# uC.net
KiCad netlist of a schematic drawn in Altium Designer
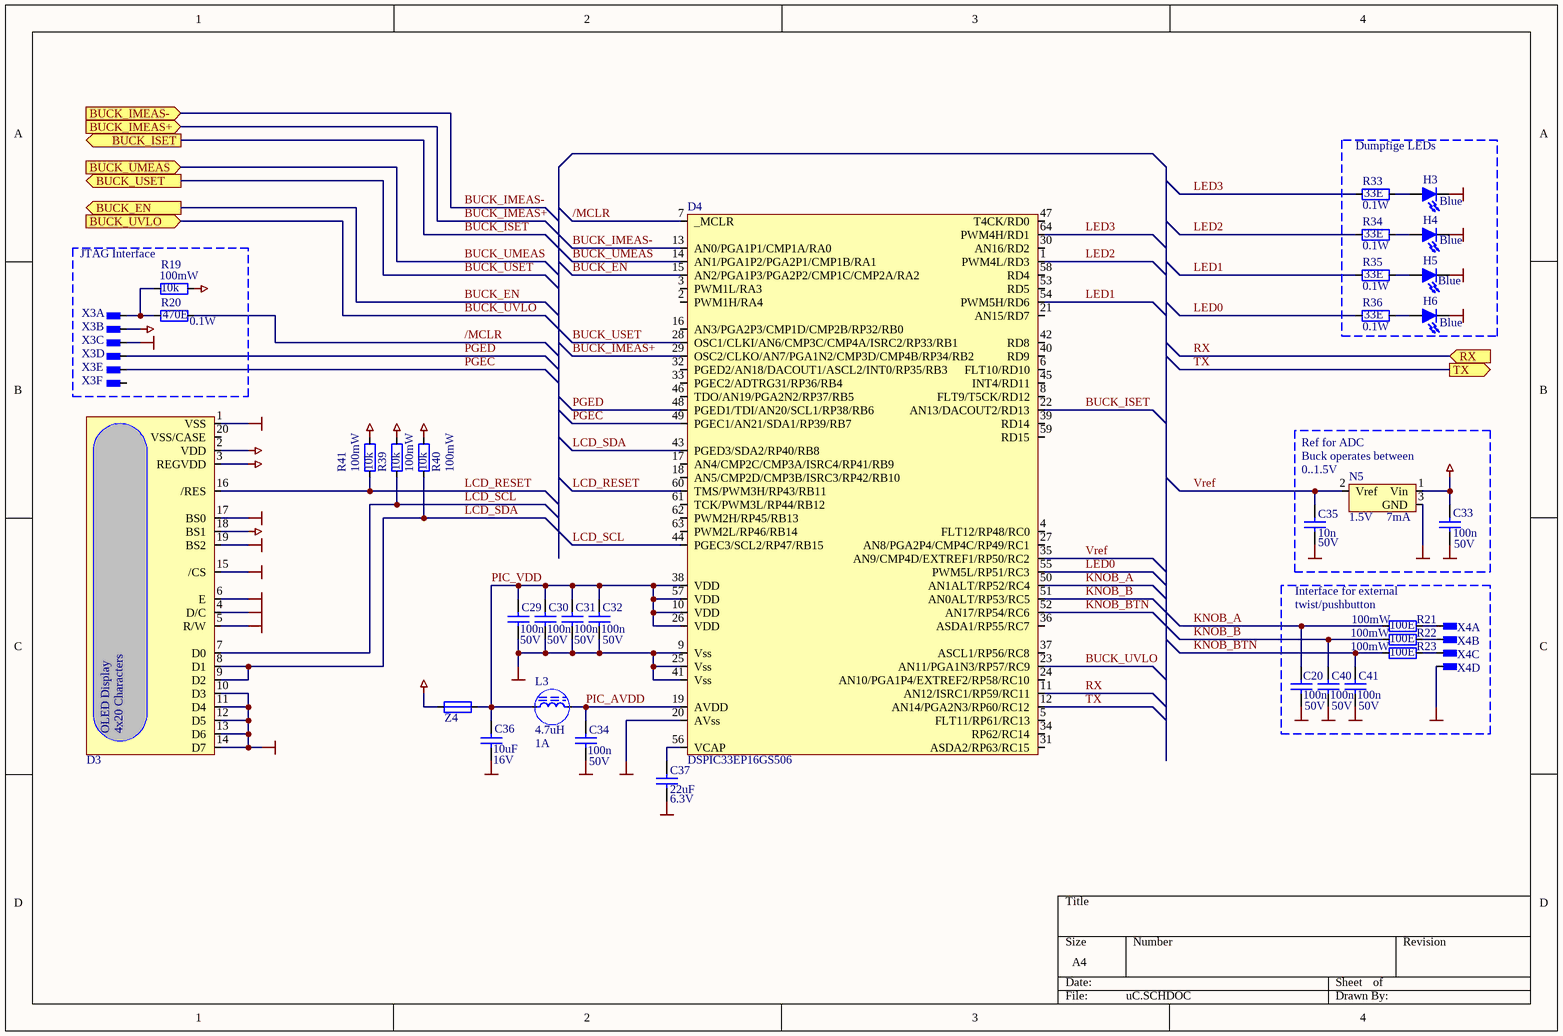
[diagram p0: uC.SCHDOC]

(export (version "E")
  (design (tool "Eeschema 10.0.6"))
  (components
    (comp (ref "C20")
      (value "C_SMD_CER_100N_50V_10%_X7R_0603")
      (footprint "SMD_0603")
      (description "SMD Capacitor")
      (fields (field (name "ALTIUM_VALUE") "100n") (field (name "VALUE2") "50V"))
      (libsource (lib "C-Capacitor") (part "C_SMD_CER_100N_50V_10%_X7R_0603"))
    )
    (comp (ref "C29")
      (value "C_SMD_CER_100N_50V_10%_X7R_0603")
      (footprint "SMD_0603")
      (description "SMD Capacitor")
      (fields (field (name "ALTIUM_VALUE") "100n") (field (name "VALUE2") "50V"))
      (libsource (lib "C-Capacitor") (part "C_SMD_CER_100N_50V_10%_X7R_0603"))
    )
    (comp (ref "C30")
      (value "C_SMD_CER_100N_50V_10%_X7R_0603")
      (footprint "SMD_0603")
      (description "SMD Capacitor")
      (fields (field (name "ALTIUM_VALUE") "100n") (field (name "VALUE2") "50V"))
      (libsource (lib "C-Capacitor") (part "C_SMD_CER_100N_50V_10%_X7R_0603"))
    )
    (comp (ref "C31")
      (value "C_SMD_CER_100N_50V_10%_X7R_0603")
      (footprint "SMD_0603")
      (description "SMD Capacitor")
      (fields (field (name "ALTIUM_VALUE") "100n") (field (name "VALUE2") "50V"))
      (libsource (lib "C-Capacitor") (part "C_SMD_CER_100N_50V_10%_X7R_0603"))
    )
    (comp (ref "C32")
      (value "C_SMD_CER_100N_50V_10%_X7R_0603")
      (footprint "SMD_0603")
      (description "SMD Capacitor")
      (fields (field (name "ALTIUM_VALUE") "100n") (field (name "VALUE2") "50V"))
      (libsource (lib "C-Capacitor") (part "C_SMD_CER_100N_50V_10%_X7R_0603"))
    )
    (comp (ref "C33")
      (value "C_SMD_CER_100N_50V_10%_X7R_0603")
      (footprint "SMD_0603")
      (description "SMD Capacitor")
      (fields (field (name "ALTIUM_VALUE") "100n") (field (name "VALUE2") "50V"))
      (libsource (lib "C-Capacitor") (part "C_SMD_CER_100N_50V_10%_X7R_0603"))
    )
    (comp (ref "C34")
      (value "C_SMD_CER_100N_50V_10%_X7R_0603")
      (footprint "SMD_0603")
      (description "SMD Capacitor")
      (fields (field (name "ALTIUM_VALUE") "100n") (field (name "VALUE2") "50V"))
      (libsource (lib "C-Capacitor") (part "C_SMD_CER_100N_50V_10%_X7R_0603"))
    )
    (comp (ref "C35")
      (value "C_SMD_CER_10N_50V_10%_X7R_0603")
      (footprint "SMD_0603")
      (description "SMD Capacitor")
      (fields (field (name "ALTIUM_VALUE") "10n") (field (name "VALUE2") "50V"))
      (libsource (lib "C-Capacitor") (part "C_SMD_CER_10N_50V_10%_X7R_0603"))
    )
    (comp (ref "C36")
      (value "C_SMD_CER_10U_16V_10%_X5R_0805")
      (footprint "SMD_0805")
      (description "SMD Capacitor")
      (fields (field (name "ALTIUM_VALUE") "10uF") (field (name "VALUE2") "16V"))
      (libsource (lib "C-Capacitor") (part "C_SMD_CER_10U_16V_10%_X5R_0805"))
    )
    (comp (ref "C37")
      (value "C_SMD_CER_22U_6V3_20%_X5R_1206")
      (footprint "SMD_1206")
      (description "SMD Capacitor")
      (fields (field (name "ALTIUM_VALUE") "22uF") (field (name "VALUE2") "6.3V"))
      (libsource (lib "C-Capacitor") (part "C_SMD_CER_22U_6V3_20%_X5R_1206"))
    )
    (comp (ref "C40")
      (value "C_SMD_CER_100N_50V_10%_X7R_0603")
      (footprint "SMD_0603")
      (description "SMD Capacitor")
      (fields (field (name "ALTIUM_VALUE") "100n") (field (name "VALUE2") "50V"))
      (libsource (lib "C-Capacitor") (part "C_SMD_CER_100N_50V_10%_X7R_0603"))
    )
    (comp (ref "C41")
      (value "C_SMD_CER_100N_50V_10%_X7R_0603")
      (footprint "SMD_0603")
      (description "SMD Capacitor")
      (fields (field (name "ALTIUM_VALUE") "100n") (field (name "VALUE2") "50V"))
      (libsource (lib "C-Capacitor") (part "C_SMD_CER_100N_50V_10%_X7R_0603"))
    )
    (comp (ref "D3")
      (value "D_LCD_80CHAR_20X4_NHD-0420CW-AR3")
      (footprint "THT_CON_P2.54_D0.9_2X10")
      (libsource (lib "D-Digital") (part "D_LCD_80CHAR_20X4_NHD-0420CW-AR3"))
    )
    (comp (ref "D4")
      (value "D_DSPIC33EP16GS506_TQFP-64")
      (footprint "SMD_TQFP-64")
      (fields (field (name "TYPE") "DSPIC33EP16GS506"))
      (libsource (lib "AM") (part "D_DSPIC33EP16GS506_TQFP-64"))
    )
    (comp (ref "H3")
      (value "H_SMD_LED_BLUE_0603")
      (footprint "SMD_0603P")
      (description "Blue LED, 5mA")
      (fields (field (name "TYPE") "Blue"))
      (libsource (lib "H-Signaling device") (part "H_SMD_LED_BLUE_0603"))
    )
    (comp (ref "H4")
      (value "H_SMD_LED_BLUE_0603")
      (footprint "SMD_0603P")
      (description "Blue LED, 5mA")
      (fields (field (name "TYPE") "Blue"))
      (libsource (lib "H-Signaling device") (part "H_SMD_LED_BLUE_0603"))
    )
    (comp (ref "H5")
      (value "H_SMD_LED_BLUE_0603")
      (footprint "SMD_0603P")
      (description "Blue LED, 5mA")
      (fields (field (name "TYPE") "Blue"))
      (libsource (lib "H-Signaling device") (part "H_SMD_LED_BLUE_0603"))
    )
    (comp (ref "H6")
      (value "H_SMD_LED_BLUE_0603")
      (footprint "SMD_0603P")
      (description "Blue LED, 5mA")
      (fields (field (name "TYPE") "Blue"))
      (libsource (lib "H-Signaling device") (part "H_SMD_LED_BLUE_0603"))
    )
    (comp (ref "L3")
      (value "L_SMD_4U7_1A_20%_0806")
      (footprint "SMD_0806")
      (description "SMD Inductor")
      (fields (field (name "ALTIUM_VALUE") "4.7uH") (field (name "VALUE2") "1A"))
      (libsource (lib "AM") (part "L_SMD_4U7_1A_20%_0806"))
    )
    (comp (ref "N5")
      (value "N_UREF_1V5_0A007_52UVRMS_ISL21080CIH315Z_SOT-23-3")
      (footprint "SMD_SOT_23_3")
      (fields (field (name "ALTIUM_VALUE") "1.5V") (field (name "VALUE2") "7mA"))
      (libsource (lib "AM") (part "N_UREF_1V5_0A007_52UVRMS_ISL21080CIH315Z_SOT-23-3"))
    )
    (comp (ref "R19")
      (value "R_SMD_THINFILM_10K_0W1_1%_50PPM_0603")
      (footprint "SMD_0603")
      (description "SMD Resistor")
      (fields (field (name "ALTIUM_VALUE") "10k") (field (name "VALUE2") "100mW"))
      (libsource (lib "R-Resistor") (part "R_SMD_THINFILM_10K_0W1_1%_50PPM_0603"))
    )
    (comp (ref "R20")
      (value "R_SMD_THINFILM_470E_0W1_1%_50PPM_0603")
      (footprint "SMD_0603")
      (description "SMD Resistor")
      (fields (field (name "ALTIUM_VALUE") "470E") (field (name "VALUE2") "0.1W"))
      (libsource (lib "AM") (part "R_SMD_THINFILM_470E_0W1_1%_50PPM_0603"))
    )
    (comp (ref "R21")
      (value "R_SMD_THINFILM_100E_0W1_1%_50PPM_0603")
      (footprint "SMD_0603")
      (description "SMD Resistor")
      (fields (field (name "ALTIUM_VALUE") "100E") (field (name "VALUE2") "100mW"))
      (libsource (lib "R-Resistor") (part "R_SMD_THINFILM_100E_0W1_1%_50PPM_0603"))
    )
    (comp (ref "R22")
      (value "R_SMD_THINFILM_100E_0W1_1%_50PPM_0603")
      (footprint "SMD_0603")
      (description "SMD Resistor")
      (fields (field (name "ALTIUM_VALUE") "100E") (field (name "VALUE2") "100mW"))
      (libsource (lib "R-Resistor") (part "R_SMD_THINFILM_100E_0W1_1%_50PPM_0603"))
    )
    (comp (ref "R23")
      (value "R_SMD_THINFILM_100E_0W1_1%_50PPM_0603")
      (footprint "SMD_0603")
      (description "SMD Resistor")
      (fields (field (name "ALTIUM_VALUE") "100E") (field (name "VALUE2") "100mW"))
      (libsource (lib "R-Resistor") (part "R_SMD_THINFILM_100E_0W1_1%_50PPM_0603"))
    )
    (comp (ref "R33")
      (value "R_SMD_THINFILM_33E_0W1_1%_50PPM_0603")
      (footprint "SMD_0603")
      (description "SMD Resistor")
      (fields (field (name "ALTIUM_VALUE") "33E") (field (name "VALUE2") "0.1W"))
      (libsource (lib "R-Resistor") (part "R_SMD_THINFILM_33E_0W1_1%_50PPM_0603"))
    )
    (comp (ref "R34")
      (value "R_SMD_THINFILM_33E_0W1_1%_50PPM_0603")
      (footprint "SMD_0603")
      (description "SMD Resistor")
      (fields (field (name "ALTIUM_VALUE") "33E") (field (name "VALUE2") "0.1W"))
      (libsource (lib "R-Resistor") (part "R_SMD_THINFILM_33E_0W1_1%_50PPM_0603"))
    )
    (comp (ref "R35")
      (value "R_SMD_THINFILM_33E_0W1_1%_50PPM_0603")
      (footprint "SMD_0603")
      (description "SMD Resistor")
      (fields (field (name "ALTIUM_VALUE") "33E") (field (name "VALUE2") "0.1W"))
      (libsource (lib "R-Resistor") (part "R_SMD_THINFILM_33E_0W1_1%_50PPM_0603"))
    )
    (comp (ref "R36")
      (value "R_SMD_THINFILM_33E_0W1_1%_50PPM_0603")
      (footprint "SMD_0603")
      (description "SMD Resistor")
      (fields (field (name "ALTIUM_VALUE") "33E") (field (name "VALUE2") "0.1W"))
      (libsource (lib "R-Resistor") (part "R_SMD_THINFILM_33E_0W1_1%_50PPM_0603"))
    )
    (comp (ref "R39")
      (value "R_SMD_THINFILM_10K_0W1_1%_50PPM_0603")
      (footprint "SMD_0603")
      (description "SMD Resistor")
      (fields (field (name "ALTIUM_VALUE") "10k") (field (name "VALUE2") "100mW"))
      (libsource (lib "AM") (part "R_SMD_THINFILM_10K_0W1_1%_50PPM_0603"))
    )
    (comp (ref "R40")
      (value "R_SMD_THINFILM_10K_0W1_1%_50PPM_0603")
      (footprint "SMD_0603")
      (description "SMD Resistor")
      (fields (field (name "ALTIUM_VALUE") "10k") (field (name "VALUE2") "100mW"))
      (libsource (lib "AM") (part "R_SMD_THINFILM_10K_0W1_1%_50PPM_0603"))
    )
    (comp (ref "R41")
      (value "R_SMD_THINFILM_10K_0W1_1%_50PPM_0603")
      (footprint "SMD_0603")
      (description "SMD Resistor")
      (fields (field (name "ALTIUM_VALUE") "10k") (field (name "VALUE2") "100mW"))
      (libsource (lib "AM") (part "R_SMD_THINFILM_10K_0W1_1%_50PPM_0603"))
    )
    (comp (ref "X3")
      (value "X_CONNECTOR_P2.54_D0.9_1X6")
      (footprint "THT_CON_P2.54_D0.9_1X6")
      (description "Pitch 2.54, Diameter 0.9mm, 1 row, 6 columns")
      (libsource (lib "AM") (part "X_CONNECTOR_P2.54_D0.9_1X6"))
    )
    (comp (ref "X4")
      (value "X_CONNECTOR_P2.54_D0.9_1X4")
      (footprint "THT_CON_P2.54_D0.9_1X4")
      (description "Pitch 2.54, Diameter 0.9mm, 1 row, 4 columns")
      (libsource (lib "AM") (part "X_CONNECTOR_P2.54_D0.9_1X4"))
    )
    (comp (ref "Z4")
      (value "Z_SMD_FERRITE_1A5_470E@100MHZ_0603")
      (footprint "SMD_0603")
      (description "FERRITE CHIP 470 OHM 1500MA 0603")
      (libsource (lib "AM") (part "Z_SMD_FERRITE_1A5_470E@100MHZ_0603"))
    )
  )
  (nets
    (net (code "1") (name "+3.3V") (class "Default")
      (node (ref "C33") (pin "2") (pinfunction "2_2") (pintype "passive"))
      (node (ref "N5") (pin "1") (pinfunction "Vin_1") (pintype "passive"))
      (node (ref "R19") (pin "2") (pinfunction "2_2") (pintype "passive"))
      (node (ref "X3") (pin "2") (pinfunction "2_2") (pintype "passive"))
      (node (ref "Z4") (pin "2") (pinfunction "2_2") (pintype "passive"))
    )
    (net (code "2") (name "+5V") (class "Default")
      (node (ref "D3") (pin "18") (pinfunction "BS1_18") (pintype "passive"))
      (node (ref "D3") (pin "2") (pinfunction "VDD_2") (pintype "passive"))
      (node (ref "D3") (pin "3") (pinfunction "REGVDD_3") (pintype "passive"))
      (node (ref "R39") (pin "2") (pinfunction "2_2") (pintype "passive"))
      (node (ref "R40") (pin "2") (pinfunction "2_2") (pintype "passive"))
      (node (ref "R41") (pin "2") (pinfunction "2_2") (pintype "passive"))
    )
    (net (code "3") (name "/BUCK_EN") (class "Default")
      (node (ref "D4") (pin "15") (pinfunction "AN2/PGA1P3/PGA2P2/CMP1C/CMP2A/RA2_15") (pintype "passive"))
    )
    (net (code "4") (name "/BUCK_IMEAS+") (class "Default")
      (node (ref "D4") (pin "29") (pinfunction "OSC2/CLKO/AN7/PGA1N2/CMP3D/CMP4B/RP34/RB2_29") (pintype "passive"))
    )
    (net (code "5") (name "/BUCK_IMEAS-") (class "Default")
      (node (ref "D4") (pin "13") (pinfunction "AN0/PGA1P1/CMP1A/RA0_13") (pintype "passive"))
    )
    (net (code "6") (name "/BUCK_ISET") (class "Default")
      (node (ref "D4") (pin "22") (pinfunction "AN13/DACOUT2/RD13_22") (pintype "passive"))
    )
    (net (code "7") (name "/BUCK_UMEAS") (class "Default")
      (node (ref "D4") (pin "14") (pinfunction "AN1/PGA1P2/PGA2P1/CMP1B/RA1_14") (pintype "passive"))
    )
    (net (code "8") (name "/BUCK_USET") (class "Default")
      (node (ref "D4") (pin "28") (pinfunction "OSC1/CLKI/AN6/CMP3C/CMP4A/ISRC2/RP33/RB1_28") (pintype "passive"))
    )
    (net (code "9") (name "/BUCK_UVLO") (class "Default")
      (node (ref "D4") (pin "23") (pinfunction "AN11/PGA1N3/RP57/RC9_23") (pintype "passive"))
    )
    (net (code "10") (name "/KNOB_A") (class "Default")
      (node (ref "C20") (pin "2") (pinfunction "2_2") (pintype "passive"))
      (node (ref "D4") (pin "50") (pinfunction "AN1ALT/RP52/RC4_50") (pintype "passive"))
      (node (ref "R21") (pin "1") (pinfunction "1_1") (pintype "passive"))
    )
    (net (code "11") (name "/KNOB_B") (class "Default")
      (node (ref "C40") (pin "2") (pinfunction "2_2") (pintype "passive"))
      (node (ref "D4") (pin "51") (pinfunction "AN0ALT/RP53/RC5_51") (pintype "passive"))
      (node (ref "R22") (pin "1") (pinfunction "1_1") (pintype "passive"))
    )
    (net (code "12") (name "/KNOB_BTN") (class "Default")
      (node (ref "C41") (pin "2") (pinfunction "2_2") (pintype "passive"))
      (node (ref "D4") (pin "52") (pinfunction "AN17/RP54/RC6_52") (pintype "passive"))
      (node (ref "R23") (pin "1") (pinfunction "1_1") (pintype "passive"))
    )
    (net (code "13") (name "/LCD_RESET") (class "Default")
      (node (ref "D3") (pin "16") (pinfunction "/RES_16") (pintype "passive"))
      (node (ref "D4") (pin "60") (pinfunction "TMS/PWM3H/RP43/RB11_60") (pintype "passive"))
      (node (ref "R41") (pin "1") (pinfunction "1_1") (pintype "passive"))
    )
    (net (code "14") (name "/LCD_SCL") (class "Default")
      (node (ref "D3") (pin "7") (pinfunction "D0_7") (pintype "passive"))
      (node (ref "D4") (pin "44") (pinfunction "PGEC3/SCL2/RP47/RB15_44") (pintype "passive"))
      (node (ref "R39") (pin "1") (pinfunction "1_1") (pintype "passive"))
    )
    (net (code "15") (name "/LCD_SDA") (class "Default")
      (node (ref "D3") (pin "8") (pinfunction "D1_8") (pintype "passive"))
      (node (ref "D3") (pin "9") (pinfunction "D2_9") (pintype "passive"))
      (node (ref "D4") (pin "43") (pinfunction "PGED3/SDA2/RP40/RB8_43") (pintype "passive"))
      (node (ref "R40") (pin "1") (pinfunction "1_1") (pintype "passive"))
    )
    (net (code "16") (name "/LED0") (class "Default")
      (node (ref "D4") (pin "55") (pinfunction "PWM5L/RP51/RC3_55") (pintype "passive"))
      (node (ref "R36") (pin "1") (pinfunction "1_1") (pintype "passive"))
    )
    (net (code "17") (name "/LED1") (class "Default")
      (node (ref "D4") (pin "54") (pinfunction "PWM5H/RD6_54") (pintype "passive"))
      (node (ref "R35") (pin "1") (pinfunction "1_1") (pintype "passive"))
    )
    (net (code "18") (name "/LED2") (class "Default")
      (node (ref "D4") (pin "1") (pinfunction "PWM4L/RD3_1") (pintype "passive"))
      (node (ref "R34") (pin "1") (pinfunction "1_1") (pintype "passive"))
    )
    (net (code "19") (name "/LED3") (class "Default")
      (node (ref "D4") (pin "64") (pinfunction "PWM4H/RD1_64") (pintype "passive"))
      (node (ref "R33") (pin "1") (pinfunction "1_1") (pintype "passive"))
    )
    (net (code "20") (name "/PGEC") (class "Default")
      (node (ref "D4") (pin "49") (pinfunction "PGEC1/AN21/SDA1/RP39/RB7_49") (pintype "passive"))
      (node (ref "X3") (pin "5") (pinfunction "5_5") (pintype "passive"))
    )
    (net (code "21") (name "/PGED") (class "Default")
      (node (ref "D4") (pin "48") (pinfunction "PGED1/TDI/AN20/SCL1/RP38/RB6_48") (pintype "passive"))
      (node (ref "X3") (pin "4") (pinfunction "4_4") (pintype "passive"))
    )
    (net (code "22") (name "/PIC_AVDD") (class "Default")
      (node (ref "C34") (pin "2") (pinfunction "2_2") (pintype "passive"))
      (node (ref "D4") (pin "19") (pinfunction "AVDD_19") (pintype "passive"))
      (node (ref "L3") (pin "2") (pinfunction "2_2") (pintype "passive"))
    )
    (net (code "23") (name "/PIC_VDD") (class "Default")
      (node (ref "C29") (pin "2") (pinfunction "2_2") (pintype "passive"))
      (node (ref "C30") (pin "2") (pinfunction "2_2") (pintype "passive"))
      (node (ref "C31") (pin "2") (pinfunction "2_2") (pintype "passive"))
      (node (ref "C32") (pin "2") (pinfunction "2_2") (pintype "passive"))
      (node (ref "C36") (pin "2") (pinfunction "2_2") (pintype "passive"))
      (node (ref "D4") (pin "10") (pinfunction "VDD_10") (pintype "passive"))
      (node (ref "D4") (pin "26") (pinfunction "VDD_26") (pintype "passive"))
      (node (ref "D4") (pin "38") (pinfunction "VDD_38") (pintype "passive"))
      (node (ref "D4") (pin "57") (pinfunction "VDD_57") (pintype "passive"))
      (node (ref "L3") (pin "1") (pinfunction "1_1") (pintype "passive"))
      (node (ref "Z4") (pin "1") (pinfunction "1_1") (pintype "passive"))
    )
    (net (code "24") (name "/RX") (class "Default")
      (node (ref "D4") (pin "11") (pinfunction "AN12/ISRC1/RP59/RC11_11") (pintype "passive"))
    )
    (net (code "25") (name "/TX") (class "Default")
      (node (ref "D4") (pin "12") (pinfunction "AN14/PGA2N3/RP60/RC12_12") (pintype "passive"))
    )
    (net (code "26") (name "/Vref") (class "Default")
      (node (ref "C35") (pin "2") (pinfunction "2_2") (pintype "passive"))
      (node (ref "D4") (pin "35") (pinfunction "AN9/CMP4D/EXTREF1/RP50/RC2_35") (pintype "passive"))
      (node (ref "N5") (pin "2") (pinfunction "Vref_2") (pintype "passive"))
    )
    (net (code "27") (name "/{slash}MCLR") (class "Default")
      (node (ref "D4") (pin "7") (pinfunction "_MCLR_7") (pintype "passive"))
      (node (ref "R20") (pin "2") (pinfunction "2_2") (pintype "passive"))
    )
    (net (code "28") (name "GND") (class "Default")
      (node (ref "C20") (pin "1") (pinfunction "1_1") (pintype "passive"))
      (node (ref "C29") (pin "1") (pinfunction "1_1") (pintype "passive"))
      (node (ref "C30") (pin "1") (pinfunction "1_1") (pintype "passive"))
      (node (ref "C31") (pin "1") (pinfunction "1_1") (pintype "passive"))
      (node (ref "C32") (pin "1") (pinfunction "1_1") (pintype "passive"))
      (node (ref "C33") (pin "1") (pinfunction "1_1") (pintype "passive"))
      (node (ref "C34") (pin "1") (pinfunction "1_1") (pintype "passive"))
      (node (ref "C35") (pin "1") (pinfunction "1_1") (pintype "passive"))
      (node (ref "C36") (pin "1") (pinfunction "1_1") (pintype "passive"))
      (node (ref "C37") (pin "1") (pinfunction "1_1") (pintype "passive"))
      (node (ref "C40") (pin "1") (pinfunction "1_1") (pintype "passive"))
      (node (ref "C41") (pin "1") (pinfunction "1_1") (pintype "passive"))
      (node (ref "D3") (pin "1") (pinfunction "VSS_1") (pintype "passive"))
      (node (ref "D3") (pin "10") (pinfunction "D3_10") (pintype "passive"))
      (node (ref "D3") (pin "11") (pinfunction "D4_11") (pintype "passive"))
      (node (ref "D3") (pin "12") (pinfunction "D5_12") (pintype "passive"))
      (node (ref "D3") (pin "13") (pinfunction "D6_13") (pintype "passive"))
      (node (ref "D3") (pin "14") (pinfunction "D7_14") (pintype "passive"))
      (node (ref "D3") (pin "15") (pinfunction "/CS_15") (pintype "passive"))
      (node (ref "D3") (pin "17") (pinfunction "BS0_17") (pintype "passive"))
      (node (ref "D3") (pin "19") (pinfunction "BS2_19") (pintype "passive"))
      (node (ref "D3") (pin "4") (pinfunction "D/C_4") (pintype "passive"))
      (node (ref "D3") (pin "5") (pinfunction "R/W_5") (pintype "passive"))
      (node (ref "D3") (pin "6") (pinfunction "E_6") (pintype "passive"))
      (node (ref "D4") (pin "20") (pinfunction "AVss_20") (pintype "passive"))
      (node (ref "D4") (pin "25") (pinfunction "Vss_25") (pintype "passive"))
      (node (ref "D4") (pin "41") (pinfunction "Vss_41") (pintype "passive"))
      (node (ref "D4") (pin "9") (pinfunction "Vss_9") (pintype "passive"))
      (node (ref "H3") (pin "2") (pinfunction "2_2") (pintype "passive"))
      (node (ref "H4") (pin "2") (pinfunction "2_2") (pintype "passive"))
      (node (ref "H5") (pin "2") (pinfunction "2_2") (pintype "passive"))
      (node (ref "H6") (pin "2") (pinfunction "2_2") (pintype "passive"))
      (node (ref "N5") (pin "3") (pinfunction "GND_3") (pintype "passive"))
      (node (ref "X3") (pin "3") (pinfunction "3_3") (pintype "passive"))
      (node (ref "X4") (pin "4") (pinfunction "4_4") (pintype "passive"))
    )
    (net (code "29") (name "Net-(D4-VCAP)") (class "Default")
      (node (ref "C37") (pin "2") (pinfunction "2_2") (pintype "passive"))
      (node (ref "D4") (pin "56") (pinfunction "VCAP_56") (pintype "passive"))
    )
    (net (code "30") (name "Net-(H3-Pad1)") (class "Default")
      (node (ref "H3") (pin "1") (pinfunction "1_1") (pintype "passive"))
      (node (ref "R33") (pin "2") (pinfunction "2_2") (pintype "passive"))
    )
    (net (code "31") (name "Net-(H4-Pad1)") (class "Default")
      (node (ref "H4") (pin "1") (pinfunction "1_1") (pintype "passive"))
      (node (ref "R34") (pin "2") (pinfunction "2_2") (pintype "passive"))
    )
    (net (code "32") (name "Net-(H5-Pad1)") (class "Default")
      (node (ref "H5") (pin "1") (pinfunction "1_1") (pintype "passive"))
      (node (ref "R35") (pin "2") (pinfunction "2_2") (pintype "passive"))
    )
    (net (code "33") (name "Net-(H6-Pad1)") (class "Default")
      (node (ref "H6") (pin "1") (pinfunction "1_1") (pintype "passive"))
      (node (ref "R36") (pin "2") (pinfunction "2_2") (pintype "passive"))
    )
    (net (code "34") (name "Net-(R19-Pad1)") (class "Default")
      (node (ref "R19") (pin "1") (pinfunction "1_1") (pintype "passive"))
      (node (ref "R20") (pin "1") (pinfunction "1_1") (pintype "passive"))
      (node (ref "X3") (pin "1") (pinfunction "1_1") (pintype "passive"))
    )
    (net (code "35") (name "Net-(R21-Pad2)") (class "Default")
      (node (ref "R21") (pin "2") (pinfunction "2_2") (pintype "passive"))
      (node (ref "X4") (pin "1") (pinfunction "1_1") (pintype "passive"))
    )
    (net (code "36") (name "Net-(R22-Pad2)") (class "Default")
      (node (ref "R22") (pin "2") (pinfunction "2_2") (pintype "passive"))
      (node (ref "X4") (pin "2") (pinfunction "2_2") (pintype "passive"))
    )
    (net (code "37") (name "Net-(R23-Pad2)") (class "Default")
      (node (ref "R23") (pin "2") (pinfunction "2_2") (pintype "passive"))
      (node (ref "X4") (pin "3") (pinfunction "3_3") (pintype "passive"))
    )
    (net (code "38") (name "unconnected-(D3-VSS{slash}CASE-Pad20)") (class "Default")
      (node (ref "D3") (pin "20") (pinfunction "VSS/CASE_20") (pintype "passive"))
    )
    (net (code "39") (name "unconnected-(D4-AN3{slash}PGA2P3{slash}CMP1D{slash}CMP2B{slash}RP32{slash}RB0-Pad16)") (class "Default")
      (node (ref "D4") (pin "16") (pinfunction "AN3/PGA2P3/CMP1D/CMP2B/RP32/RB0_16") (pintype "passive"))
    )
    (net (code "40") (name "unconnected-(D4-AN4{slash}CMP2C{slash}CMP3A{slash}ISRC4{slash}RP41{slash}RB9-Pad17)") (class "Default")
      (node (ref "D4") (pin "17") (pinfunction "AN4/CMP2C/CMP3A/ISRC4/RP41/RB9_17") (pintype "passive"))
    )
    (net (code "41") (name "unconnected-(D4-AN5{slash}CMP2D{slash}CMP3B{slash}ISRC3{slash}RP42{slash}RB10-Pad18)") (class "Default")
      (node (ref "D4") (pin "18") (pinfunction "AN5/CMP2D/CMP3B/ISRC3/RP42/RB10_18") (pintype "passive"))
    )
    (net (code "42") (name "unconnected-(D4-AN8{slash}PGA2P4{slash}CMP4C{slash}RP49{slash}RC1-Pad27)") (class "Default")
      (node (ref "D4") (pin "27") (pinfunction "AN8/PGA2P4/CMP4C/RP49/RC1_27") (pintype "passive"))
    )
    (net (code "43") (name "unconnected-(D4-AN10{slash}PGA1P4{slash}EXTREF2{slash}RP58{slash}RC10-Pad24)") (class "Default")
      (node (ref "D4") (pin "24") (pinfunction "AN10/PGA1P4/EXTREF2/RP58/RC10_24") (pintype "passive"))
    )
    (net (code "44") (name "unconnected-(D4-AN15{slash}RD7-Pad21)") (class "Default")
      (node (ref "D4") (pin "21") (pinfunction "AN15/RD7_21") (pintype "passive"))
    )
    (net (code "45") (name "unconnected-(D4-AN16{slash}RD2-Pad30)") (class "Default")
      (node (ref "D4") (pin "30") (pinfunction "AN16/RD2_30") (pintype "passive"))
    )
    (net (code "46") (name "unconnected-(D4-ASCL1{slash}RP56{slash}RC8-Pad37)") (class "Default")
      (node (ref "D4") (pin "37") (pinfunction "ASCL1/RP56/RC8_37") (pintype "passive"))
    )
    (net (code "47") (name "unconnected-(D4-ASDA1{slash}RP55{slash}RC7-Pad36)") (class "Default")
      (node (ref "D4") (pin "36") (pinfunction "ASDA1/RP55/RC7_36") (pintype "passive"))
    )
    (net (code "48") (name "unconnected-(D4-ASDA2{slash}RP63{slash}RC15-Pad31)") (class "Default")
      (node (ref "D4") (pin "31") (pinfunction "ASDA2/RP63/RC15_31") (pintype "passive"))
    )
    (net (code "49") (name "unconnected-(D4-FLT9{slash}T5CK{slash}RD12-Pad8)") (class "Default")
      (node (ref "D4") (pin "8") (pinfunction "FLT9/T5CK/RD12_8") (pintype "passive"))
    )
    (net (code "50") (name "unconnected-(D4-FLT10{slash}RD10-Pad6)") (class "Default")
      (node (ref "D4") (pin "6") (pinfunction "FLT10/RD10_6") (pintype "passive"))
    )
    (net (code "51") (name "unconnected-(D4-FLT11{slash}RP61{slash}RC13-Pad5)") (class "Default")
      (node (ref "D4") (pin "5") (pinfunction "FLT11/RP61/RC13_5") (pintype "passive"))
    )
    (net (code "52") (name "unconnected-(D4-FLT12{slash}RP48{slash}RC0-Pad4)") (class "Default")
      (node (ref "D4") (pin "4") (pinfunction "FLT12/RP48/RC0_4") (pintype "passive"))
    )
    (net (code "53") (name "unconnected-(D4-INT4{slash}RD11-Pad45)") (class "Default")
      (node (ref "D4") (pin "45") (pinfunction "INT4/RD11_45") (pintype "passive"))
    )
    (net (code "54") (name "unconnected-(D4-PGEC2{slash}ADTRG31{slash}RP36{slash}RB4-Pad33)") (class "Default")
      (node (ref "D4") (pin "33") (pinfunction "PGEC2/ADTRG31/RP36/RB4_33") (pintype "passive"))
    )
    (net (code "55") (name "unconnected-(D4-PGED2{slash}AN18{slash}DACOUT1{slash}ASCL2{slash}INT0{slash}RP35{slash}RB3-Pad32)") (class "Default")
      (node (ref "D4") (pin "32") (pinfunction "PGED2/AN18/DACOUT1/ASCL2/INT0/RP35/RB3_32") (pintype "passive"))
    )
    (net (code "56") (name "unconnected-(D4-PWM1H{slash}RA4-Pad2)") (class "Default")
      (node (ref "D4") (pin "2") (pinfunction "PWM1H/RA4_2") (pintype "passive"))
    )
    (net (code "57") (name "unconnected-(D4-PWM1L{slash}RA3-Pad3)") (class "Default")
      (node (ref "D4") (pin "3") (pinfunction "PWM1L/RA3_3") (pintype "passive"))
    )
    (net (code "58") (name "unconnected-(D4-PWM2H{slash}RP45{slash}RB13-Pad62)") (class "Default")
      (node (ref "D4") (pin "62") (pinfunction "PWM2H/RP45/RB13_62") (pintype "passive"))
    )
    (net (code "59") (name "unconnected-(D4-PWM2L{slash}RP46{slash}RB14-Pad63)") (class "Default")
      (node (ref "D4") (pin "63") (pinfunction "PWM2L/RP46/RB14_63") (pintype "passive"))
    )
    (net (code "60") (name "unconnected-(D4-RD4-Pad58)") (class "Default")
      (node (ref "D4") (pin "58") (pinfunction "RD4_58") (pintype "passive"))
    )
    (net (code "61") (name "unconnected-(D4-RD5-Pad53)") (class "Default")
      (node (ref "D4") (pin "53") (pinfunction "RD5_53") (pintype "passive"))
    )
    (net (code "62") (name "unconnected-(D4-RD8-Pad42)") (class "Default")
      (node (ref "D4") (pin "42") (pinfunction "RD8_42") (pintype "passive"))
    )
    (net (code "63") (name "unconnected-(D4-RD9-Pad40)") (class "Default")
      (node (ref "D4") (pin "40") (pinfunction "RD9_40") (pintype "passive"))
    )
    (net (code "64") (name "unconnected-(D4-RD14-Pad39)") (class "Default")
      (node (ref "D4") (pin "39") (pinfunction "RD14_39") (pintype "passive"))
    )
    (net (code "65") (name "unconnected-(D4-RD15-Pad59)") (class "Default")
      (node (ref "D4") (pin "59") (pinfunction "RD15_59") (pintype "passive"))
    )
    (net (code "66") (name "unconnected-(D4-RP62{slash}RC14-Pad34)") (class "Default")
      (node (ref "D4") (pin "34") (pinfunction "RP62/RC14_34") (pintype "passive"))
    )
    (net (code "67") (name "unconnected-(D4-T4CK{slash}RD0-Pad47)") (class "Default")
      (node (ref "D4") (pin "47") (pinfunction "T4CK/RD0_47") (pintype "passive"))
    )
    (net (code "68") (name "unconnected-(D4-TCK{slash}PWM3L{slash}RP44{slash}RB12-Pad61)") (class "Default")
      (node (ref "D4") (pin "61") (pinfunction "TCK/PWM3L/RP44/RB12_61") (pintype "passive"))
    )
    (net (code "69") (name "unconnected-(D4-TDO{slash}AN19{slash}PGA2N2{slash}RP37{slash}RB5-Pad46)") (class "Default")
      (node (ref "D4") (pin "46") (pinfunction "TDO/AN19/PGA2N2/RP37/RB5_46") (pintype "passive"))
    )
    (net (code "70") (name "unconnected-(X3-Pad6)") (class "Default")
      (node (ref "X3") (pin "6") (pinfunction "6_6") (pintype "passive"))
    )
  )
)
